# C64_PSU_Z66.net
KiCad netlist of a schematic drawn in EAGLE
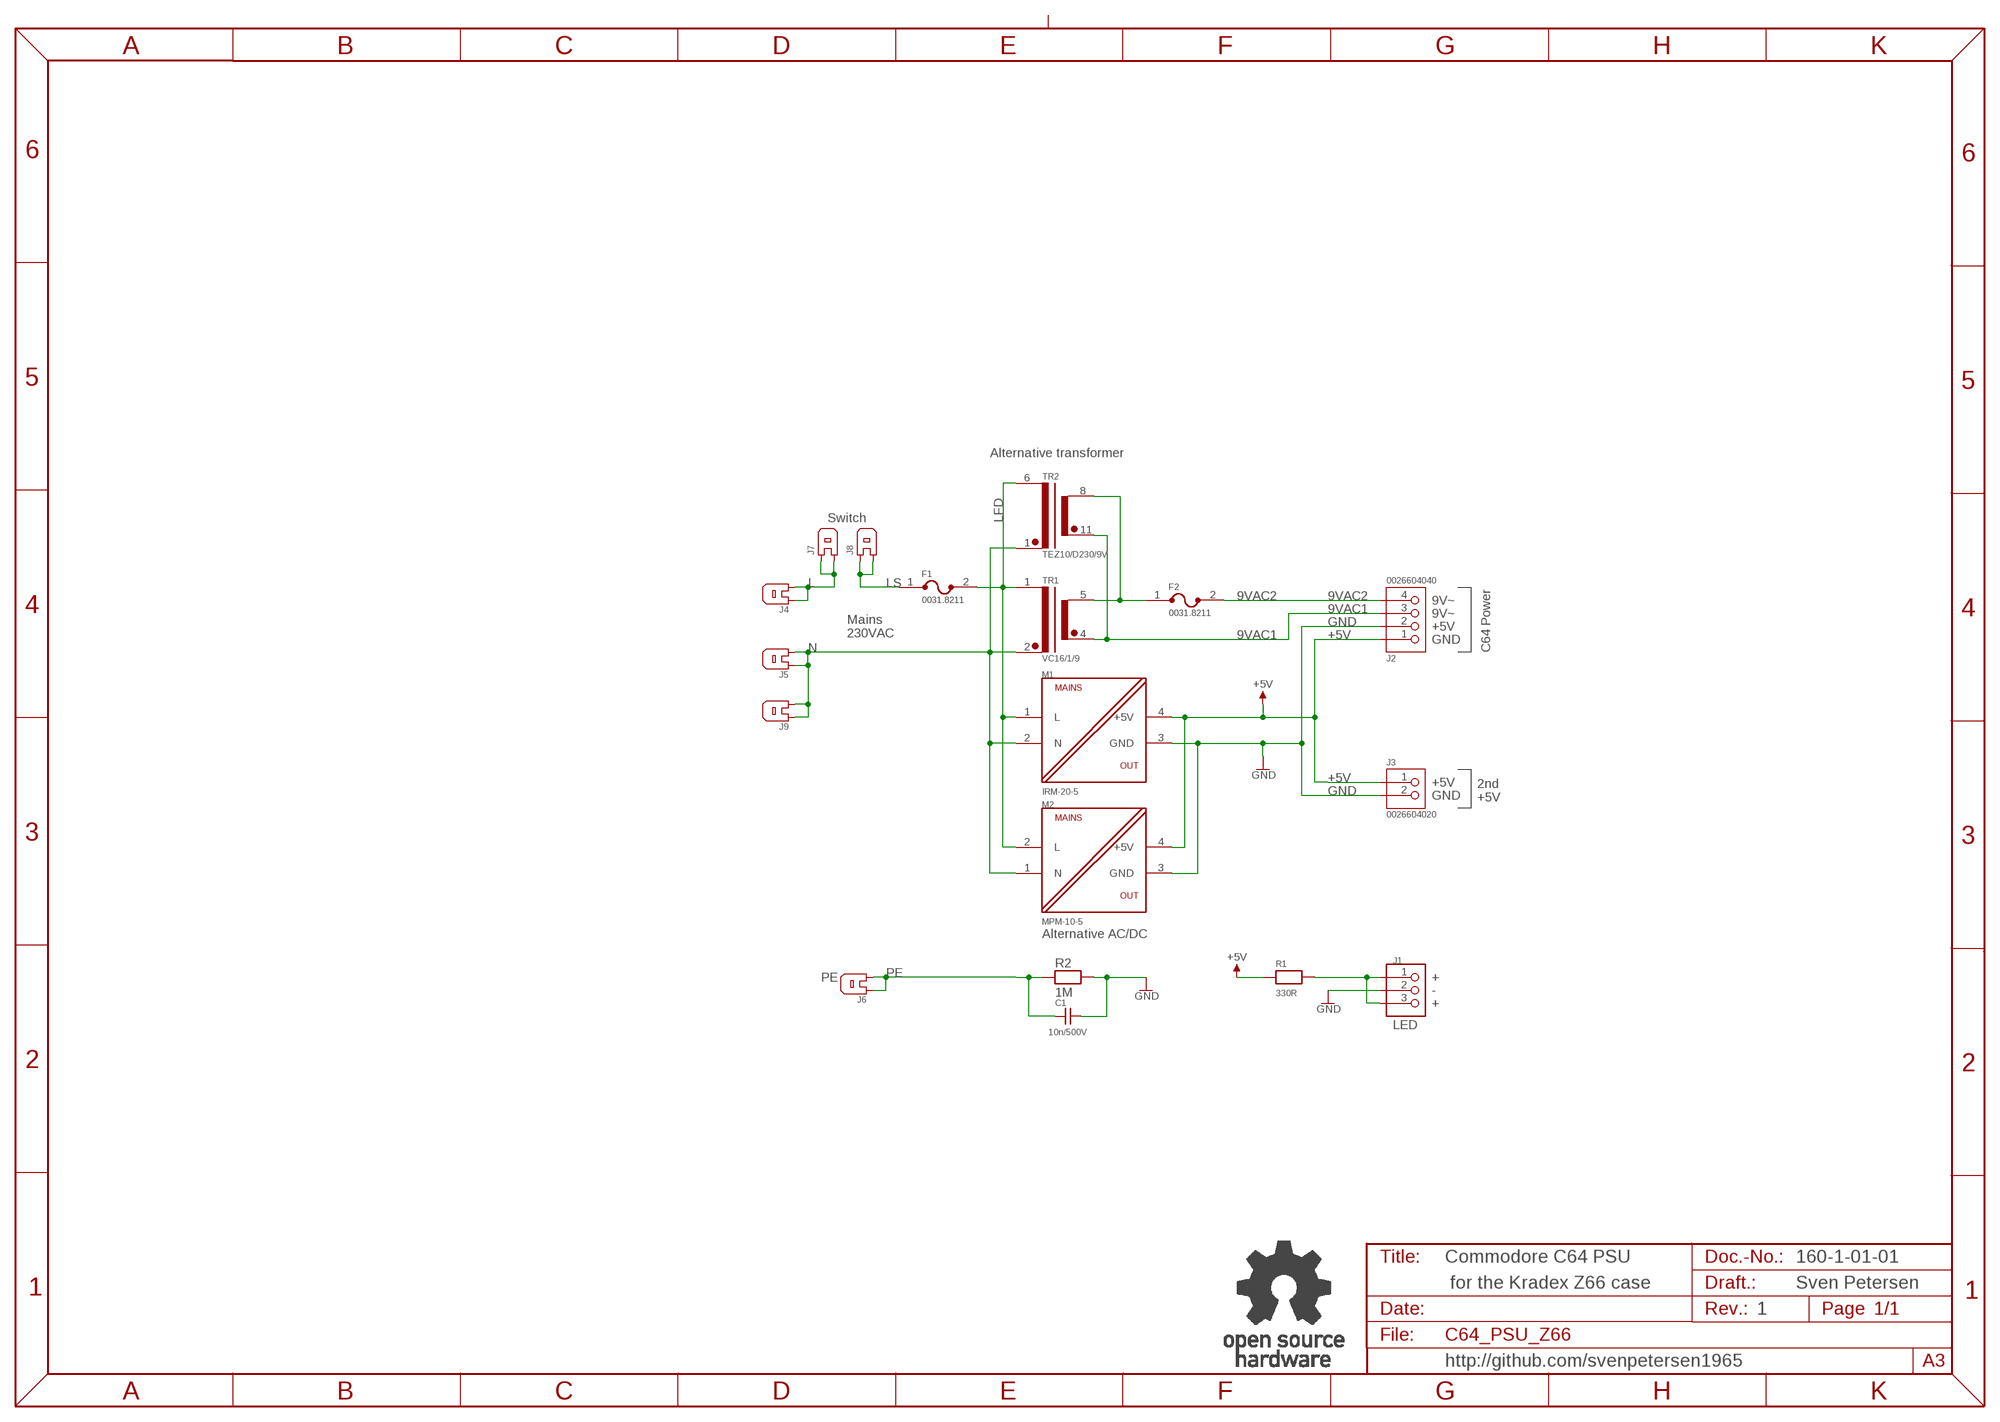
[diagram p0: schematic, sheet 1]

(export (version "E")
  (design (tool "Eeschema 10.0.6"))
  (components
    (comp (ref "C1")
      (value "10n/500V")
      (footprint "eagle-import:C-5")
      (libsource (lib "eagle-import") (part "CAP02"))
    )
    (comp (ref "F1")
      (value "0031.8211")
      (footprint "eagle-import:0031.8211")
      (libsource (lib "eagle-import") (part "0031.8211"))
    )
    (comp (ref "F2")
      (value "0031.8211")
      (footprint "eagle-import:0031.8211")
      (libsource (lib "eagle-import") (part "0031.8211"))
    )
    (comp (ref "J1")
      (value "PINHD-1X3")
      (footprint "eagle-import:1X03")
      (libsource (lib "eagle-import") (part "PINHD-1X3"))
    )
    (comp (ref "J2")
      (value "0026604040")
      (footprint "eagle-import:SPOX_3.96_4P")
      (libsource (lib "eagle-import") (part "0026604040"))
    )
    (comp (ref "J3")
      (value "0026604020")
      (footprint "eagle-import:SPOX_3.96_2P")
      (libsource (lib "eagle-import") (part "0026604020"))
    )
    (comp (ref "J4")
      (value "FLA6,3")
      (footprint "eagle-import:FLA6,3")
      (libsource (lib "eagle-import") (part "FLA6,3"))
    )
    (comp (ref "J5")
      (value "FLA6,3")
      (footprint "eagle-import:FLA6,3")
      (libsource (lib "eagle-import") (part "FLA6,3"))
    )
    (comp (ref "J6")
      (value "FLA6,3")
      (footprint "eagle-import:FLA6,3")
      (libsource (lib "eagle-import") (part "FLA6,3"))
    )
    (comp (ref "J7")
      (value "FLA6,3")
      (footprint "eagle-import:FLA6,3")
      (libsource (lib "eagle-import") (part "FLA6,3"))
    )
    (comp (ref "J8")
      (value "FLA6,3")
      (footprint "eagle-import:FLA6,3")
      (libsource (lib "eagle-import") (part "FLA6,3"))
    )
    (comp (ref "J9")
      (value "FLA6,3")
      (footprint "eagle-import:FLA6,3")
      (libsource (lib "eagle-import") (part "FLA6,3"))
    )
    (comp (ref "M1")
      (value "IRM-20-5")
      (footprint "eagle-import:IRM-5-20")
      (libsource (lib "eagle-import") (part "IRM-20-5"))
    )
    (comp (ref "M2")
      (value "MPM-10-5")
      (footprint "eagle-import:MPM10")
      (libsource (lib "eagle-import") (part "MPM-10-5"))
    )
    (comp (ref "R1")
      (value "330R")
      (footprint "eagle-import:R-10")
      (libsource (lib "eagle-import") (part "RES04"))
    )
    (comp (ref "R2")
      (value "1M")
      (footprint "eagle-import:R-10")
      (libsource (lib "eagle-import") (part "RES04"))
    )
    (comp (ref "TR1")
      (value "VC16/1/9")
      (footprint "eagle-import:VC16_1_9")
      (libsource (lib "eagle-import") (part "VC16/1/9"))
    )
    (comp (ref "TR2")
      (value "TEZ10/D230/9V")
      (footprint "eagle-import:TEZ10")
      (libsource (lib "eagle-import") (part "TEZ10/D230/9V"))
    )
    (comp (ref "U$8")
      (value "OPEN_SOURCE_HW")
      (footprint "eagle-import:OPENHW")
      (libsource (lib "eagle-import") (part "OPEN_SOURCE_HW"))
    )
  )
  (nets
    (net (code "1") (name "+5V") (class "Default")
      (node (ref "J2") (pin "1") (pinfunction "1_1") (pintype "passive"))
      (node (ref "J3") (pin "1") (pinfunction "1_1") (pintype "passive"))
      (node (ref "M1") (pin "4") (pinfunction "+5V_4") (pintype "power_in"))
      (node (ref "M2") (pin "4") (pinfunction "+5V_4") (pintype "power_in"))
      (node (ref "R1") (pin "1") (pinfunction "1_1") (pintype "passive"))
    )
    (net (code "2") (name "/9VAC1") (class "Default")
      (node (ref "J2") (pin "3") (pinfunction "3_3") (pintype "passive"))
      (node (ref "TR1") (pin "4") (pinfunction "SEC12_4") (pintype "passive"))
      (node (ref "TR2") (pin "11") (pinfunction "SEC12_11") (pintype "passive"))
    )
    (net (code "3") (name "/9VAC2") (class "Default")
      (node (ref "F2") (pin "2") (pinfunction "2_2") (pintype "passive"))
      (node (ref "J2") (pin "4") (pinfunction "4_4") (pintype "passive"))
    )
    (net (code "4") (name "/L") (class "Default")
      (node (ref "J4") (pin "1") (pinfunction "1_1") (pintype "passive"))
      (node (ref "J4") (pin "2") (pinfunction "2_2") (pintype "passive"))
      (node (ref "J7") (pin "1") (pinfunction "1_1") (pintype "passive"))
      (node (ref "J7") (pin "2") (pinfunction "2_2") (pintype "passive"))
    )
    (net (code "5") (name "/LFD") (class "Default")
      (node (ref "F1") (pin "2") (pinfunction "2_2") (pintype "passive"))
      (node (ref "M1") (pin "1") (pinfunction "L_1") (pintype "power_in"))
      (node (ref "M2") (pin "2") (pinfunction "L_2") (pintype "power_in"))
      (node (ref "TR1") (pin "1") (pinfunction "PRI1_1") (pintype "passive"))
      (node (ref "TR2") (pin "6") (pinfunction "PRI1_6") (pintype "passive"))
    )
    (net (code "6") (name "/LS") (class "Default")
      (node (ref "F1") (pin "1") (pinfunction "1_1") (pintype "passive"))
      (node (ref "J8") (pin "1") (pinfunction "1_1") (pintype "passive"))
      (node (ref "J8") (pin "2") (pinfunction "2_2") (pintype "passive"))
    )
    (net (code "7") (name "/N") (class "Default")
      (node (ref "J5") (pin "1") (pinfunction "1_1") (pintype "passive"))
      (node (ref "J5") (pin "2") (pinfunction "2_2") (pintype "passive"))
      (node (ref "J9") (pin "1") (pinfunction "1_1") (pintype "passive"))
      (node (ref "J9") (pin "2") (pinfunction "2_2") (pintype "passive"))
      (node (ref "M1") (pin "2") (pinfunction "N_2") (pintype "power_in"))
      (node (ref "M2") (pin "1") (pinfunction "N_1") (pintype "power_in"))
      (node (ref "TR1") (pin "2") (pinfunction "PRI2_2") (pintype "passive"))
      (node (ref "TR2") (pin "1") (pinfunction "PRI2_1") (pintype "passive"))
    )
    (net (code "8") (name "/PE") (class "Default")
      (node (ref "C1") (pin "1") (pinfunction "1_1") (pintype "passive"))
      (node (ref "J6") (pin "1") (pinfunction "1_1") (pintype "passive"))
      (node (ref "J6") (pin "2") (pinfunction "2_2") (pintype "passive"))
      (node (ref "R2") (pin "1") (pinfunction "1_1") (pintype "passive"))
    )
    (net (code "9") (name "GND") (class "Default")
      (node (ref "C1") (pin "2") (pinfunction "2_2") (pintype "passive"))
      (node (ref "J1") (pin "2") (pinfunction "2_2") (pintype "passive"))
      (node (ref "J2") (pin "2") (pinfunction "2_2") (pintype "passive"))
      (node (ref "J3") (pin "2") (pinfunction "2_2") (pintype "passive"))
      (node (ref "M1") (pin "3") (pinfunction "GND_3") (pintype "power_in"))
      (node (ref "M2") (pin "3") (pinfunction "GND_3") (pintype "power_in"))
      (node (ref "R2") (pin "2") (pinfunction "2_2") (pintype "passive"))
    )
    (net (code "10") (name "Net-(J1-Pad1)") (class "Default")
      (node (ref "J1") (pin "1") (pinfunction "1_1") (pintype "passive"))
      (node (ref "J1") (pin "3") (pinfunction "3_3") (pintype "passive"))
      (node (ref "R1") (pin "2") (pinfunction "2_2") (pintype "passive"))
    )
    (net (code "11") (name "Net-(TR1-SEC11)") (class "Default")
      (node (ref "F2") (pin "1") (pinfunction "1_1") (pintype "passive"))
      (node (ref "TR1") (pin "5") (pinfunction "SEC11_5") (pintype "passive"))
      (node (ref "TR2") (pin "8") (pinfunction "SEC11_8") (pintype "passive"))
    )
  )
)
